# DACs.net
KiCad netlist of a schematic drawn in Altium Designer
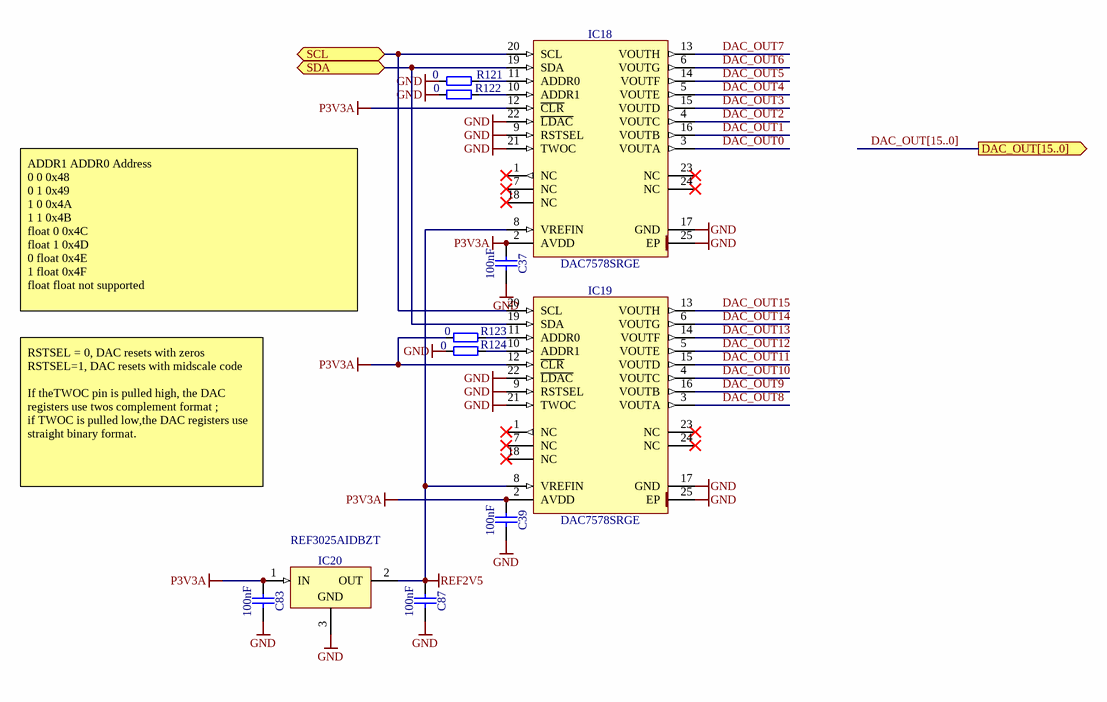
[diagram p0: DACs.SchDoc]

(export (version "E")
  (design (tool "Eeschema 10.0.6"))
  (components
    (comp (ref "C37")
      (value "100nF")
      (footprint "CAPC0603X33N")
      (description "Non-polarised capacitor")
      (fields
        (field (name "PART NUMBER") "CC0201_100NF_6.3V_10%_X5R")
        (field (name "VOLTAGE") "6.3V")
        (field (name "AUTHOR") "CERN DEM JLC")
      )
      (libsource (lib "Capacitors") (part "Capacitor - non polarized"))
    )
    (comp (ref "C39")
      (value "100nF")
      (footprint "CAPC0603X33N")
      (description "Non-polarised capacitor")
      (fields
        (field (name "PART NUMBER") "CC0201_100NF_6.3V_10%_X5R")
        (field (name "VOLTAGE") "6.3V")
        (field (name "AUTHOR") "CERN DEM JLC")
      )
      (libsource (lib "Capacitors") (part "Capacitor - non polarized"))
    )
    (comp (ref "C83")
      (value "100nF")
      (footprint "CAPC0603X33N")
      (description "Non-polarised capacitor")
      (fields
        (field (name "PART NUMBER") "CC0201_100NF_6.3V_10%_X5R")
        (field (name "VOLTAGE") "6.3V")
        (field (name "AUTHOR") "CERN DEM JLC")
      )
      (libsource (lib "Capacitors") (part "Capacitor - non polarized"))
    )
    (comp (ref "C87")
      (value "100nF")
      (footprint "CAPC0603X33N")
      (description "Non-polarised capacitor")
      (fields
        (field (name "PART NUMBER") "CC0201_100NF_6.3V_10%_X5R")
        (field (name "VOLTAGE") "6.3V")
        (field (name "AUTHOR") "CERN DEM JLC")
      )
      (libsource (lib "Capacitors") (part "Capacitor - non polarized"))
    )
    (comp (ref "IC18")
      (value "DAC7578SRGE")
      (footprint "QFN50P400X400X100-25N-S280")
      (fields (field (name "MANUFACTURER") "TEXAS INSTRUMENTS") (field (name "AUTHOR") "CERN DEM MR"))
      (libsource (lib "ICs And Semiconductors") (part "DAC7578SRGE"))
    )
    (comp (ref "IC19")
      (value "DAC7578SRGE")
      (footprint "QFN50P400X400X100-25N-S280")
      (fields (field (name "MANUFACTURER") "TEXAS INSTRUMENTS") (field (name "AUTHOR") "CERN DEM MR"))
      (libsource (lib "ICs And Semiconductors") (part "DAC7578SRGE"))
    )
    (comp (ref "IC20")
      (value "REF3025AIDBZT")
      (footprint "SOT95P237X112-3N")
      (description "3-Terminal Regulator 1=IN 2=OUT 3=GND")
      (fields (field (name "MANUFACTURER") "TEXAS INSTRUMENTS") (field (name "AUTHOR") "CERN DEM JLC"))
      (libsource (lib "ICs And Semiconductors") (part "REG3 1IN-2OUT-3GND"))
    )
    (comp (ref "R121")
      (value "0")
      (footprint "RESC1005X40N")
      (description "Resistor")
      (fields
        (field (name "PART NUMBER") "R0402_0R_JUMPER")
        (field (name "MANUFACTURER") "GENERIC")
        (field (name "AUTHOR") "CERN DEM JLC")
      )
      (libsource (lib "Resistors") (part "Resistor"))
    )
    (comp (ref "R122")
      (value "0")
      (footprint "RESC1005X40N")
      (description "Resistor")
      (fields
        (field (name "PART NUMBER") "R0402_0R_JUMPER")
        (field (name "MANUFACTURER") "GENERIC")
        (field (name "AUTHOR") "CERN DEM JLC")
      )
      (libsource (lib "Resistors") (part "Resistor"))
    )
    (comp (ref "R123")
      (value "0")
      (footprint "RESC1005X40N")
      (description "Resistor")
      (fields
        (field (name "PART NUMBER") "R0402_0R_JUMPER")
        (field (name "MANUFACTURER") "GENERIC")
        (field (name "AUTHOR") "CERN DEM JLC")
      )
      (libsource (lib "Resistors") (part "Resistor"))
    )
    (comp (ref "R124")
      (value "0")
      (footprint "RESC1005X40N")
      (description "Resistor")
      (fields
        (field (name "PART NUMBER") "R0402_0R_JUMPER")
        (field (name "MANUFACTURER") "GENERIC")
        (field (name "AUTHOR") "CERN DEM JLC")
      )
      (libsource (lib "Resistors") (part "Resistor"))
    )
  )
  (nets
    (net (code "1") (name "/DAC_OUT0") (class "Default")
      (node (ref "IC18") (pin "3") (pinfunction "VOUTA_3") (pintype "output"))
    )
    (net (code "2") (name "/DAC_OUT1") (class "Default")
      (node (ref "IC18") (pin "16") (pinfunction "VOUTB_16") (pintype "output"))
    )
    (net (code "3") (name "/DAC_OUT2") (class "Default")
      (node (ref "IC18") (pin "4") (pinfunction "VOUTC_4") (pintype "output"))
    )
    (net (code "4") (name "/DAC_OUT3") (class "Default")
      (node (ref "IC18") (pin "15") (pinfunction "VOUTD_15") (pintype "output"))
    )
    (net (code "5") (name "/DAC_OUT4") (class "Default")
      (node (ref "IC18") (pin "5") (pinfunction "VOUTE_5") (pintype "output"))
    )
    (net (code "6") (name "/DAC_OUT5") (class "Default")
      (node (ref "IC18") (pin "14") (pinfunction "VOUTF_14") (pintype "output"))
    )
    (net (code "7") (name "/DAC_OUT6") (class "Default")
      (node (ref "IC18") (pin "6") (pinfunction "VOUTG_6") (pintype "output"))
    )
    (net (code "8") (name "/DAC_OUT7") (class "Default")
      (node (ref "IC18") (pin "13") (pinfunction "VOUTH_13") (pintype "output"))
    )
    (net (code "9") (name "/DAC_OUT8") (class "Default")
      (node (ref "IC19") (pin "3") (pinfunction "VOUTA_3") (pintype "output"))
    )
    (net (code "10") (name "/DAC_OUT9") (class "Default")
      (node (ref "IC19") (pin "16") (pinfunction "VOUTB_16") (pintype "output"))
    )
    (net (code "11") (name "/DAC_OUT10") (class "Default")
      (node (ref "IC19") (pin "4") (pinfunction "VOUTC_4") (pintype "output"))
    )
    (net (code "12") (name "/DAC_OUT11") (class "Default")
      (node (ref "IC19") (pin "15") (pinfunction "VOUTD_15") (pintype "output"))
    )
    (net (code "13") (name "/DAC_OUT12") (class "Default")
      (node (ref "IC19") (pin "5") (pinfunction "VOUTE_5") (pintype "output"))
    )
    (net (code "14") (name "/DAC_OUT13") (class "Default")
      (node (ref "IC19") (pin "14") (pinfunction "VOUTF_14") (pintype "output"))
    )
    (net (code "15") (name "/DAC_OUT14") (class "Default")
      (node (ref "IC19") (pin "6") (pinfunction "VOUTG_6") (pintype "output"))
    )
    (net (code "16") (name "/DAC_OUT15") (class "Default")
      (node (ref "IC19") (pin "13") (pinfunction "VOUTH_13") (pintype "output"))
    )
    (net (code "18") (name "/SCL") (class "Default")
      (node (ref "IC18") (pin "20") (pinfunction "SCL_20") (pintype "input"))
      (node (ref "IC19") (pin "20") (pinfunction "SCL_20") (pintype "input"))
    )
    (net (code "19") (name "/SDA") (class "Default")
      (node (ref "IC18") (pin "19") (pinfunction "SDA_19") (pintype "input"))
      (node (ref "IC19") (pin "19") (pinfunction "SDA_19") (pintype "input"))
    )
    (net (code "20") (name "GND") (class "Default")
      (node (ref "C37") (pin "2") (pinfunction "2_2") (pintype "passive"))
      (node (ref "C39") (pin "2") (pinfunction "2_2") (pintype "passive"))
      (node (ref "C83") (pin "2") (pinfunction "2_2") (pintype "passive"))
      (node (ref "C87") (pin "2") (pinfunction "2_2") (pintype "passive"))
      (node (ref "IC18") (pin "17") (pinfunction "GND_17") (pintype "power_in"))
      (node (ref "IC18") (pin "21") (pinfunction "TWOC_21") (pintype "input"))
      (node (ref "IC18") (pin "22") (pinfunction "~{LDAC}_22") (pintype "input"))
      (node (ref "IC18") (pin "25") (pinfunction "EP_25") (pintype "power_in"))
      (node (ref "IC18") (pin "9") (pinfunction "RSTSEL_9") (pintype "input"))
      (node (ref "IC19") (pin "17") (pinfunction "GND_17") (pintype "power_in"))
      (node (ref "IC19") (pin "21") (pinfunction "TWOC_21") (pintype "input"))
      (node (ref "IC19") (pin "22") (pinfunction "~{LDAC}_22") (pintype "input"))
      (node (ref "IC19") (pin "25") (pinfunction "EP_25") (pintype "power_in"))
      (node (ref "IC19") (pin "9") (pinfunction "RSTSEL_9") (pintype "input"))
      (node (ref "IC20") (pin "3") (pinfunction "GND_3") (pintype "power_in"))
      (node (ref "R121") (pin "1") (pinfunction "1_1") (pintype "passive"))
      (node (ref "R122") (pin "1") (pinfunction "1_1") (pintype "passive"))
      (node (ref "R124") (pin "1") (pinfunction "1_1") (pintype "passive"))
    )
    (net (code "21") (name "Net-(IC18-ADDR0)") (class "Default")
      (node (ref "IC18") (pin "11") (pinfunction "ADDR0_11") (pintype "input"))
      (node (ref "R121") (pin "2") (pinfunction "2_2") (pintype "passive"))
    )
    (net (code "22") (name "Net-(IC18-ADDR1)") (class "Default")
      (node (ref "IC18") (pin "10") (pinfunction "ADDR1_10") (pintype "input"))
      (node (ref "R122") (pin "2") (pinfunction "2_2") (pintype "passive"))
    )
    (net (code "23") (name "Net-(IC19-ADDR0)") (class "Default")
      (node (ref "IC19") (pin "11") (pinfunction "ADDR0_11") (pintype "input"))
      (node (ref "R123") (pin "2") (pinfunction "2_2") (pintype "passive"))
    )
    (net (code "24") (name "Net-(IC19-ADDR1)") (class "Default")
      (node (ref "IC19") (pin "10") (pinfunction "ADDR1_10") (pintype "input"))
      (node (ref "R124") (pin "2") (pinfunction "2_2") (pintype "passive"))
    )
    (net (code "25") (name "P3V3A") (class "Default")
      (node (ref "C37") (pin "1") (pinfunction "1_1") (pintype "passive"))
      (node (ref "C39") (pin "1") (pinfunction "1_1") (pintype "passive"))
      (node (ref "C83") (pin "1") (pinfunction "1_1") (pintype "passive"))
      (node (ref "IC18") (pin "12") (pinfunction "~{CLR}_12") (pintype "input"))
      (node (ref "IC18") (pin "2") (pinfunction "AVDD_2") (pintype "power_in"))
      (node (ref "IC19") (pin "12") (pinfunction "~{CLR}_12") (pintype "input"))
      (node (ref "IC19") (pin "2") (pinfunction "AVDD_2") (pintype "power_in"))
      (node (ref "IC20") (pin "1") (pinfunction "IN_1") (pintype "input"))
      (node (ref "R123") (pin "1") (pinfunction "1_1") (pintype "passive"))
    )
    (net (code "26") (name "REF2V5") (class "Default")
      (node (ref "C87") (pin "1") (pinfunction "1_1") (pintype "passive"))
      (node (ref "IC18") (pin "8") (pinfunction "VREFIN_8") (pintype "input"))
      (node (ref "IC19") (pin "8") (pinfunction "VREFIN_8") (pintype "input"))
      (node (ref "IC20") (pin "2") (pinfunction "OUT_2") (pintype "power_in"))
    )
    (net (code "27") (name "unconnected-(IC18-NC-Pad1)") (class "Default")
      (node (ref "IC18") (pin "1") (pinfunction "NC_1") (pintype "output+no_connect"))
    )
    (net (code "28") (name "unconnected-(IC18-NC-Pad7)") (class "Default")
      (node (ref "IC18") (pin "7") (pinfunction "NC_7") (pintype "passive+no_connect"))
    )
    (net (code "29") (name "unconnected-(IC18-NC-Pad18)") (class "Default")
      (node (ref "IC18") (pin "18") (pinfunction "NC_18") (pintype "passive+no_connect"))
    )
    (net (code "30") (name "unconnected-(IC18-NC-Pad23)") (class "Default")
      (node (ref "IC18") (pin "23") (pinfunction "NC_23") (pintype "passive+no_connect"))
    )
    (net (code "31") (name "unconnected-(IC18-NC-Pad24)") (class "Default")
      (node (ref "IC18") (pin "24") (pinfunction "NC_24") (pintype "passive+no_connect"))
    )
    (net (code "32") (name "unconnected-(IC19-NC-Pad1)") (class "Default")
      (node (ref "IC19") (pin "1") (pinfunction "NC_1") (pintype "output+no_connect"))
    )
    (net (code "33") (name "unconnected-(IC19-NC-Pad7)") (class "Default")
      (node (ref "IC19") (pin "7") (pinfunction "NC_7") (pintype "passive+no_connect"))
    )
    (net (code "34") (name "unconnected-(IC19-NC-Pad18)") (class "Default")
      (node (ref "IC19") (pin "18") (pinfunction "NC_18") (pintype "passive+no_connect"))
    )
    (net (code "35") (name "unconnected-(IC19-NC-Pad23)") (class "Default")
      (node (ref "IC19") (pin "23") (pinfunction "NC_23") (pintype "passive+no_connect"))
    )
    (net (code "36") (name "unconnected-(IC19-NC-Pad24)") (class "Default")
      (node (ref "IC19") (pin "24") (pinfunction "NC_24") (pintype "passive+no_connect"))
    )
  )
)
